# shield.net
KiCad netlist of a schematic drawn in EAGLE
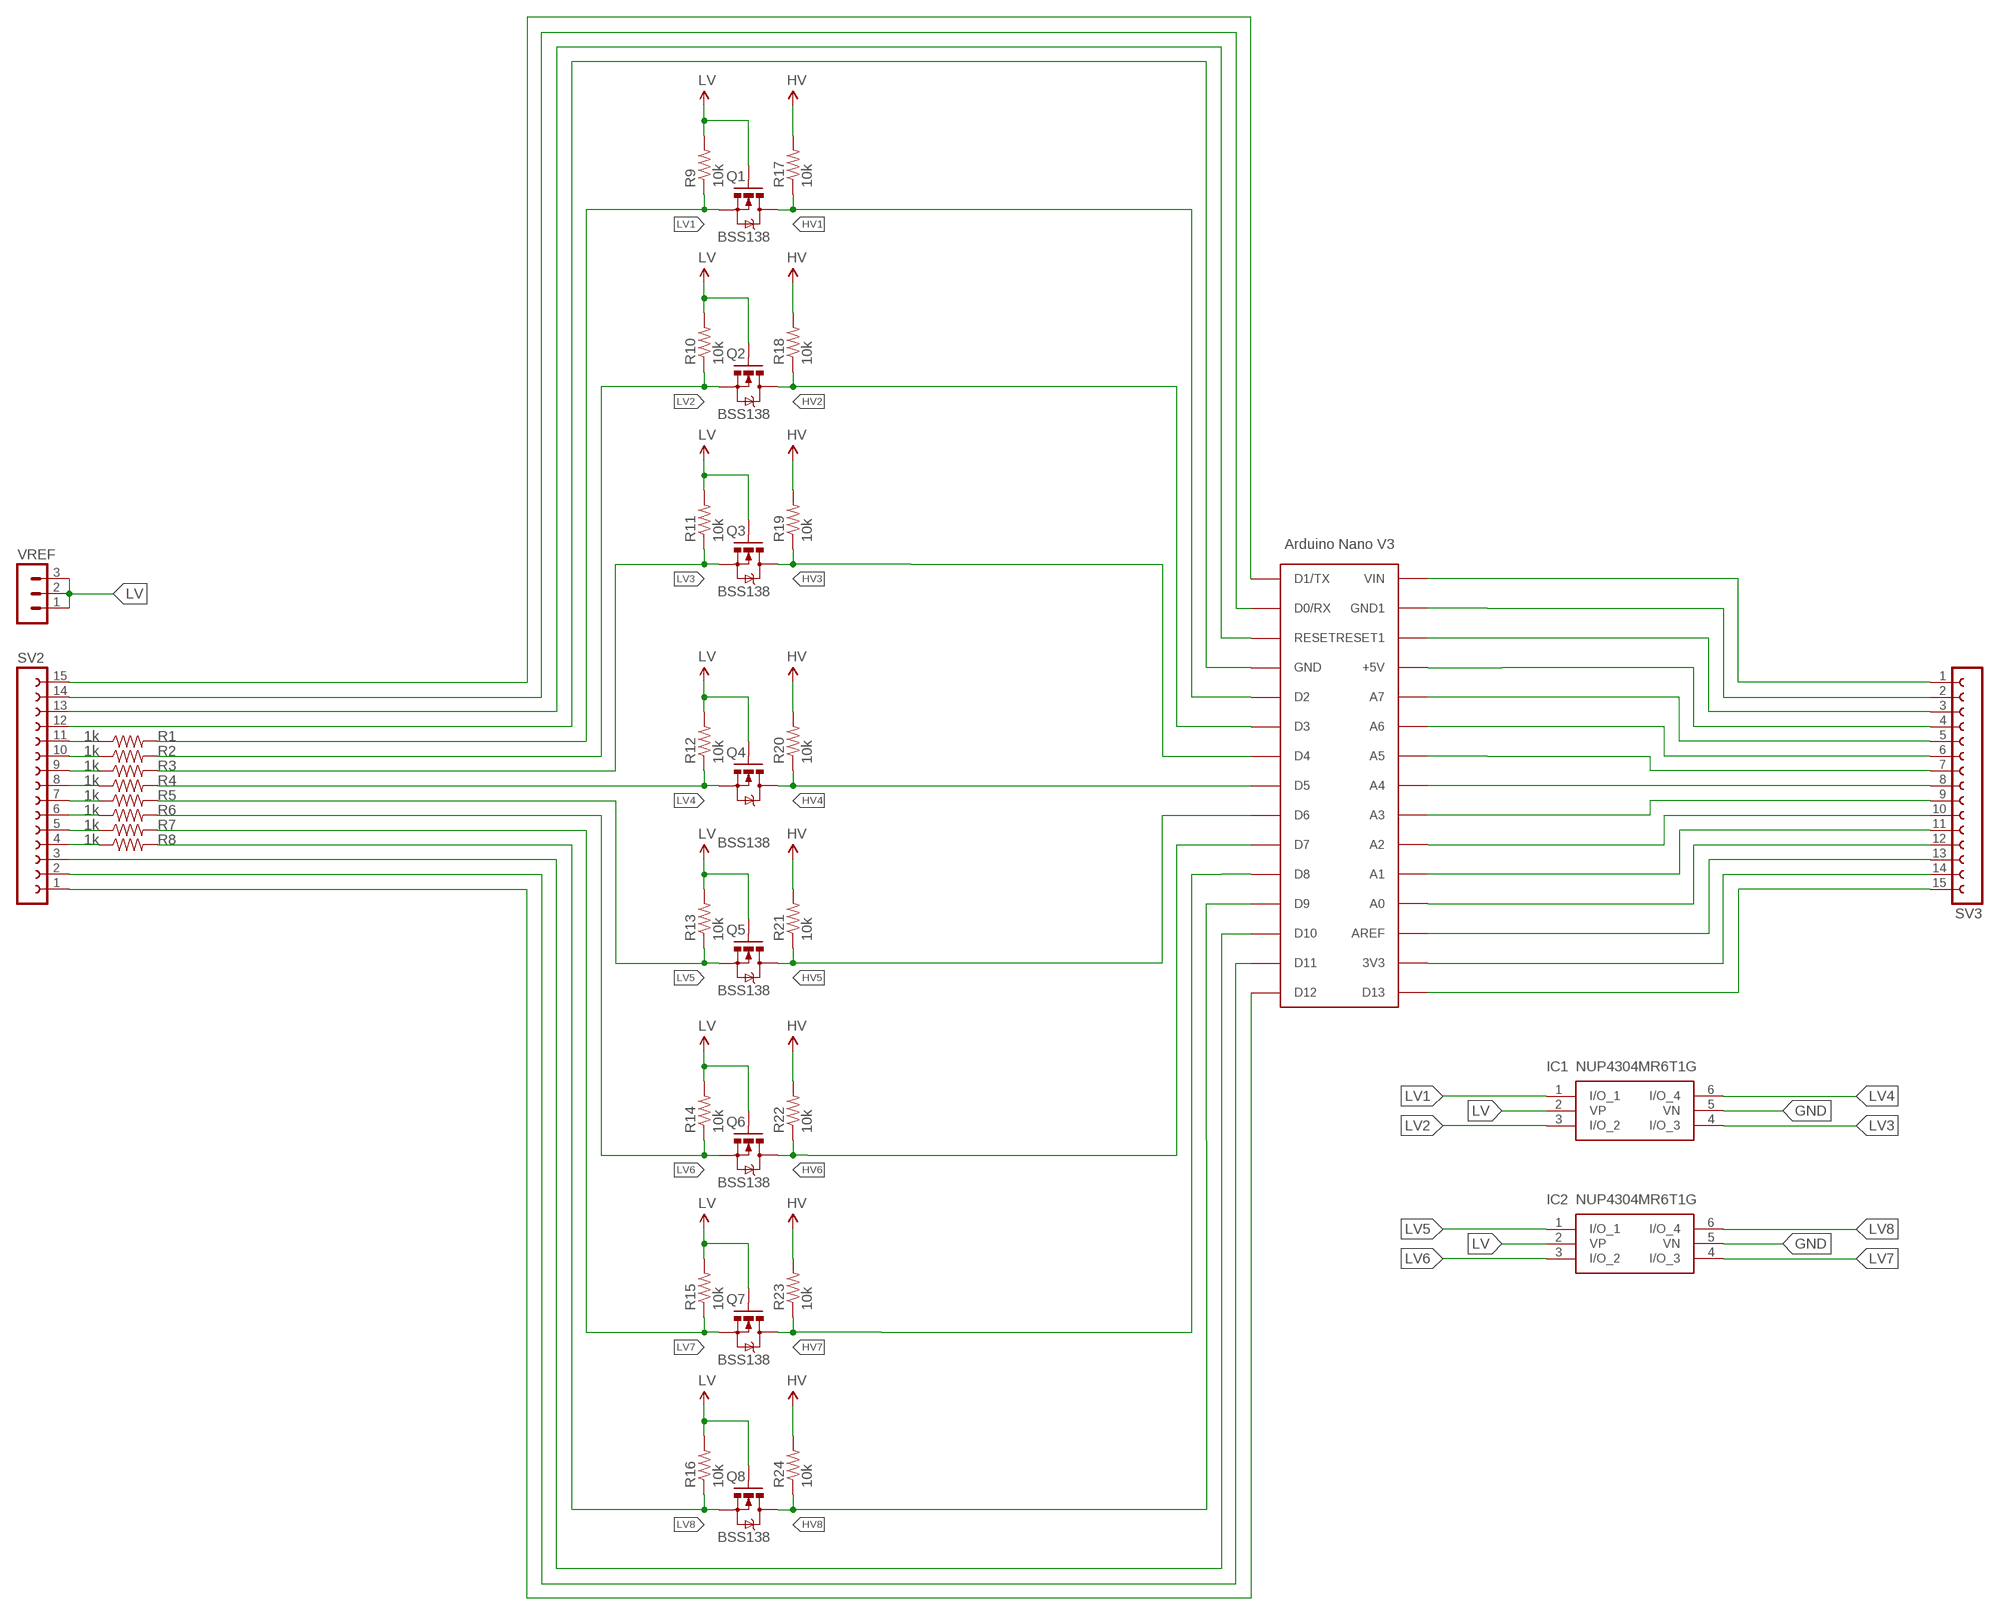
[diagram p0: schematic, sheet 1]

(export (version "E")
  (design (tool "Eeschema 10.0.6"))
  (components
    (comp (ref "IC1")
      (value "NUP4304MR6T1G")
      (footprint "eagle-import:SOT95P275X110-6N")
      (fields
        (field (name "MOUSER_PART_NUMBER") "863-NUP4304MR6T1G")
        (field (name "RS_PART_NUMBER") "8024310")
      )
      (libsource (lib "eagle-import") (part "NUP4304MR6T1G"))
    )
    (comp (ref "IC2")
      (value "NUP4304MR6T1G")
      (footprint "eagle-import:SOT95P275X110-6N")
      (fields
        (field (name "MOUSER_PART_NUMBER") "863-NUP4304MR6T1G")
        (field (name "RS_PART_NUMBER") "8024310")
      )
      (libsource (lib "eagle-import") (part "NUP4304MR6T1G"))
    )
    (comp (ref "Q1")
      (value "BSS138")
      (footprint "eagle-import:SOT23-3")
      (libsource (lib "eagle-import") (part "MOSFET-NCHANNELSMD"))
    )
    (comp (ref "Q2")
      (value "BSS138")
      (footprint "eagle-import:SOT23-3")
      (libsource (lib "eagle-import") (part "MOSFET-NCHANNELSMD"))
    )
    (comp (ref "Q3")
      (value "BSS138")
      (footprint "eagle-import:SOT23-3")
      (libsource (lib "eagle-import") (part "MOSFET-NCHANNELSMD"))
    )
    (comp (ref "Q4")
      (value "BSS138")
      (footprint "eagle-import:SOT23-3")
      (libsource (lib "eagle-import") (part "MOSFET-NCHANNELSMD"))
    )
    (comp (ref "Q5")
      (value "BSS138")
      (footprint "eagle-import:SOT23-3")
      (libsource (lib "eagle-import") (part "MOSFET-NCHANNELSMD"))
    )
    (comp (ref "Q6")
      (value "BSS138")
      (footprint "eagle-import:SOT23-3")
      (libsource (lib "eagle-import") (part "MOSFET-NCHANNELSMD"))
    )
    (comp (ref "Q7")
      (value "BSS138")
      (footprint "eagle-import:SOT23-3")
      (libsource (lib "eagle-import") (part "MOSFET-NCHANNELSMD"))
    )
    (comp (ref "Q8")
      (value "BSS138")
      (footprint "eagle-import:SOT23-3")
      (libsource (lib "eagle-import") (part "MOSFET-NCHANNELSMD"))
    )
    (comp (ref "R1")
      (value "1k")
      (footprint "eagle-import:R0402")
      (libsource (lib "eagle-import") (part "R-US_R0402"))
    )
    (comp (ref "R2")
      (value "1k")
      (footprint "eagle-import:R0402")
      (libsource (lib "eagle-import") (part "R-US_R0402"))
    )
    (comp (ref "R3")
      (value "1k")
      (footprint "eagle-import:R0402")
      (libsource (lib "eagle-import") (part "R-US_R0402"))
    )
    (comp (ref "R4")
      (value "1k")
      (footprint "eagle-import:R0402")
      (libsource (lib "eagle-import") (part "R-US_R0402"))
    )
    (comp (ref "R5")
      (value "1k")
      (footprint "eagle-import:R0402")
      (libsource (lib "eagle-import") (part "R-US_R0402"))
    )
    (comp (ref "R6")
      (value "1k")
      (footprint "eagle-import:R0402")
      (libsource (lib "eagle-import") (part "R-US_R0402"))
    )
    (comp (ref "R7")
      (value "1k")
      (footprint "eagle-import:R0402")
      (libsource (lib "eagle-import") (part "R-US_R0402"))
    )
    (comp (ref "R8")
      (value "1k")
      (footprint "eagle-import:R0402")
      (libsource (lib "eagle-import") (part "R-US_R0402"))
    )
    (comp (ref "R9")
      (value "10k")
      (footprint "eagle-import:R0402")
      (libsource (lib "eagle-import") (part "R-US_R0402"))
    )
    (comp (ref "R10")
      (value "10k")
      (footprint "eagle-import:R0402")
      (libsource (lib "eagle-import") (part "R-US_R0402"))
    )
    (comp (ref "R11")
      (value "10k")
      (footprint "eagle-import:R0402")
      (libsource (lib "eagle-import") (part "R-US_R0402"))
    )
    (comp (ref "R12")
      (value "10k")
      (footprint "eagle-import:R0402")
      (libsource (lib "eagle-import") (part "R-US_R0402"))
    )
    (comp (ref "R13")
      (value "10k")
      (footprint "eagle-import:R0402")
      (libsource (lib "eagle-import") (part "R-US_R0402"))
    )
    (comp (ref "R14")
      (value "10k")
      (footprint "eagle-import:R0402")
      (libsource (lib "eagle-import") (part "R-US_R0402"))
    )
    (comp (ref "R15")
      (value "10k")
      (footprint "eagle-import:R0402")
      (libsource (lib "eagle-import") (part "R-US_R0402"))
    )
    (comp (ref "R16")
      (value "10k")
      (footprint "eagle-import:R0402")
      (libsource (lib "eagle-import") (part "R-US_R0402"))
    )
    (comp (ref "R17")
      (value "10k")
      (footprint "eagle-import:R0402")
      (libsource (lib "eagle-import") (part "R-US_R0402"))
    )
    (comp (ref "R18")
      (value "10k")
      (footprint "eagle-import:R0402")
      (libsource (lib "eagle-import") (part "R-US_R0402"))
    )
    (comp (ref "R19")
      (value "10k")
      (footprint "eagle-import:R0402")
      (libsource (lib "eagle-import") (part "R-US_R0402"))
    )
    (comp (ref "R20")
      (value "10k")
      (footprint "eagle-import:R0402")
      (libsource (lib "eagle-import") (part "R-US_R0402"))
    )
    (comp (ref "R21")
      (value "10k")
      (footprint "eagle-import:R0402")
      (libsource (lib "eagle-import") (part "R-US_R0402"))
    )
    (comp (ref "R22")
      (value "10k")
      (footprint "eagle-import:R0402")
      (libsource (lib "eagle-import") (part "R-US_R0402"))
    )
    (comp (ref "R23")
      (value "10k")
      (footprint "eagle-import:R0402")
      (libsource (lib "eagle-import") (part "R-US_R0402"))
    )
    (comp (ref "R24")
      (value "10k")
      (footprint "eagle-import:R0402")
      (libsource (lib "eagle-import") (part "R-US_R0402"))
    )
    (comp (ref "SV2")
      (value "FE15-1")
      (footprint "eagle-import:FE15")
      (libsource (lib "eagle-import") (part "FE15-1"))
    )
    (comp (ref "SV3")
      (value "FE15-1")
      (footprint "eagle-import:FE15")
      (libsource (lib "eagle-import") (part "FE15-1"))
    )
    (comp (ref "U1")
      (value "CRE-LIB1-NL_ARDUINONANO40-MIL-HOLES")
      (footprint "eagle-import:ARDUINO-NANO-32-40MIL-HOLES")
      (libsource (lib "eagle-import") (part "CRE-LIB1-NL_ARDUINONANO40-MIL-HOLES"))
    )
    (comp (ref "VREF")
      (value "MA03-1")
      (footprint "eagle-import:MA03-1")
      (libsource (lib "eagle-import") (part "MA03-1"))
    )
  )
  (nets
    (net (code "1") (name "GND") (class "Default")
      (node (ref "IC1") (pin "5") (pinfunction "VN_5") (pintype "bidirectional"))
      (node (ref "IC2") (pin "5") (pinfunction "VN_5") (pintype "bidirectional"))
      (node (ref "SV2") (pin "12") (pinfunction "12_12") (pintype "passive"))
      (node (ref "SV3") (pin "2") (pinfunction "2_2") (pintype "passive"))
      (node (ref "U1") (pin "GND") (pinfunction "GND_GND") (pintype "bidirectional"))
      (node (ref "U1") (pin "GND1") (pinfunction "GND1_GND1") (pintype "bidirectional"))
    )
    (net (code "2") (name "HV") (class "Default")
      (node (ref "R17") (pin "2") (pinfunction "2_2") (pintype "passive"))
      (node (ref "R18") (pin "2") (pinfunction "2_2") (pintype "passive"))
      (node (ref "R19") (pin "2") (pinfunction "2_2") (pintype "passive"))
      (node (ref "R20") (pin "2") (pinfunction "2_2") (pintype "passive"))
      (node (ref "R21") (pin "2") (pinfunction "2_2") (pintype "passive"))
      (node (ref "R22") (pin "2") (pinfunction "2_2") (pintype "passive"))
      (node (ref "R23") (pin "2") (pinfunction "2_2") (pintype "passive"))
      (node (ref "R24") (pin "2") (pinfunction "2_2") (pintype "passive"))
      (node (ref "SV3") (pin "4") (pinfunction "4_4") (pintype "passive"))
      (node (ref "U1") (pin "+5V") (pinfunction "+5V_+5V") (pintype "bidirectional"))
    )
    (net (code "3") (name "HV1") (class "Default")
      (node (ref "Q1") (pin "3") (pinfunction "D_3") (pintype "passive"))
      (node (ref "R17") (pin "1") (pinfunction "1_1") (pintype "passive"))
      (node (ref "U1") (pin "D2") (pinfunction "D2_D2") (pintype "bidirectional"))
    )
    (net (code "4") (name "HV2") (class "Default")
      (node (ref "Q2") (pin "3") (pinfunction "D_3") (pintype "passive"))
      (node (ref "R18") (pin "1") (pinfunction "1_1") (pintype "passive"))
      (node (ref "U1") (pin "D3") (pinfunction "D3_D3") (pintype "bidirectional"))
    )
    (net (code "5") (name "HV3") (class "Default")
      (node (ref "Q3") (pin "3") (pinfunction "D_3") (pintype "passive"))
      (node (ref "R19") (pin "1") (pinfunction "1_1") (pintype "passive"))
      (node (ref "U1") (pin "D4") (pinfunction "D4_D4") (pintype "bidirectional"))
    )
    (net (code "6") (name "HV4") (class "Default")
      (node (ref "Q4") (pin "3") (pinfunction "D_3") (pintype "passive"))
      (node (ref "R20") (pin "1") (pinfunction "1_1") (pintype "passive"))
      (node (ref "U1") (pin "D5") (pinfunction "D5_D5") (pintype "bidirectional"))
    )
    (net (code "7") (name "HV5") (class "Default")
      (node (ref "Q5") (pin "3") (pinfunction "D_3") (pintype "passive"))
      (node (ref "R21") (pin "1") (pinfunction "1_1") (pintype "passive"))
      (node (ref "U1") (pin "D6") (pinfunction "D6_D6") (pintype "bidirectional"))
    )
    (net (code "8") (name "HV6") (class "Default")
      (node (ref "Q6") (pin "3") (pinfunction "D_3") (pintype "passive"))
      (node (ref "R22") (pin "1") (pinfunction "1_1") (pintype "passive"))
      (node (ref "U1") (pin "D7") (pinfunction "D7_D7") (pintype "bidirectional"))
    )
    (net (code "9") (name "HV7") (class "Default")
      (node (ref "Q7") (pin "3") (pinfunction "D_3") (pintype "passive"))
      (node (ref "R23") (pin "1") (pinfunction "1_1") (pintype "passive"))
      (node (ref "U1") (pin "D8") (pinfunction "D8_D8") (pintype "bidirectional"))
    )
    (net (code "10") (name "HV8") (class "Default")
      (node (ref "Q8") (pin "3") (pinfunction "D_3") (pintype "passive"))
      (node (ref "R24") (pin "1") (pinfunction "1_1") (pintype "passive"))
      (node (ref "U1") (pin "D9") (pinfunction "D9_D9") (pintype "bidirectional"))
    )
    (net (code "11") (name "LV") (class "Default")
      (node (ref "IC1") (pin "2") (pinfunction "VP_2") (pintype "bidirectional"))
      (node (ref "IC2") (pin "2") (pinfunction "VP_2") (pintype "bidirectional"))
      (node (ref "Q1") (pin "1") (pinfunction "G_1") (pintype "passive"))
      (node (ref "Q2") (pin "1") (pinfunction "G_1") (pintype "passive"))
      (node (ref "Q3") (pin "1") (pinfunction "G_1") (pintype "passive"))
      (node (ref "Q4") (pin "1") (pinfunction "G_1") (pintype "passive"))
      (node (ref "Q5") (pin "1") (pinfunction "G_1") (pintype "passive"))
      (node (ref "Q6") (pin "1") (pinfunction "G_1") (pintype "passive"))
      (node (ref "Q7") (pin "1") (pinfunction "G_1") (pintype "passive"))
      (node (ref "Q8") (pin "1") (pinfunction "G_1") (pintype "passive"))
      (node (ref "R10") (pin "2") (pinfunction "2_2") (pintype "passive"))
      (node (ref "R11") (pin "2") (pinfunction "2_2") (pintype "passive"))
      (node (ref "R12") (pin "2") (pinfunction "2_2") (pintype "passive"))
      (node (ref "R13") (pin "2") (pinfunction "2_2") (pintype "passive"))
      (node (ref "R14") (pin "2") (pinfunction "2_2") (pintype "passive"))
      (node (ref "R15") (pin "2") (pinfunction "2_2") (pintype "passive"))
      (node (ref "R16") (pin "2") (pinfunction "2_2") (pintype "passive"))
      (node (ref "R9") (pin "2") (pinfunction "2_2") (pintype "passive"))
      (node (ref "VREF") (pin "1") (pinfunction "1_1") (pintype "passive"))
      (node (ref "VREF") (pin "2") (pinfunction "2_2") (pintype "passive"))
      (node (ref "VREF") (pin "3") (pinfunction "3_3") (pintype "passive"))
    )
    (net (code "12") (name "LV1") (class "Default")
      (node (ref "IC1") (pin "1") (pinfunction "I/O_1_1") (pintype "bidirectional"))
      (node (ref "Q1") (pin "2") (pinfunction "S_2") (pintype "passive"))
      (node (ref "R1") (pin "2") (pinfunction "2_2") (pintype "passive"))
      (node (ref "R9") (pin "1") (pinfunction "1_1") (pintype "passive"))
    )
    (net (code "13") (name "LV2") (class "Default")
      (node (ref "IC1") (pin "3") (pinfunction "I/O_2_3") (pintype "bidirectional"))
      (node (ref "Q2") (pin "2") (pinfunction "S_2") (pintype "passive"))
      (node (ref "R10") (pin "1") (pinfunction "1_1") (pintype "passive"))
      (node (ref "R2") (pin "2") (pinfunction "2_2") (pintype "passive"))
    )
    (net (code "14") (name "LV3") (class "Default")
      (node (ref "IC1") (pin "4") (pinfunction "I/O_3_4") (pintype "bidirectional"))
      (node (ref "Q3") (pin "2") (pinfunction "S_2") (pintype "passive"))
      (node (ref "R11") (pin "1") (pinfunction "1_1") (pintype "passive"))
      (node (ref "R3") (pin "2") (pinfunction "2_2") (pintype "passive"))
    )
    (net (code "15") (name "LV4") (class "Default")
      (node (ref "IC1") (pin "6") (pinfunction "I/O_4_6") (pintype "bidirectional"))
      (node (ref "Q4") (pin "2") (pinfunction "S_2") (pintype "passive"))
      (node (ref "R12") (pin "1") (pinfunction "1_1") (pintype "passive"))
      (node (ref "R4") (pin "2") (pinfunction "2_2") (pintype "passive"))
    )
    (net (code "16") (name "LV5") (class "Default")
      (node (ref "IC2") (pin "1") (pinfunction "I/O_1_1") (pintype "bidirectional"))
      (node (ref "Q5") (pin "2") (pinfunction "S_2") (pintype "passive"))
      (node (ref "R13") (pin "1") (pinfunction "1_1") (pintype "passive"))
      (node (ref "R5") (pin "2") (pinfunction "2_2") (pintype "passive"))
    )
    (net (code "17") (name "LV6") (class "Default")
      (node (ref "IC2") (pin "3") (pinfunction "I/O_2_3") (pintype "bidirectional"))
      (node (ref "Q6") (pin "2") (pinfunction "S_2") (pintype "passive"))
      (node (ref "R14") (pin "1") (pinfunction "1_1") (pintype "passive"))
      (node (ref "R6") (pin "2") (pinfunction "2_2") (pintype "passive"))
    )
    (net (code "18") (name "LV7") (class "Default")
      (node (ref "IC2") (pin "4") (pinfunction "I/O_3_4") (pintype "bidirectional"))
      (node (ref "Q7") (pin "2") (pinfunction "S_2") (pintype "passive"))
      (node (ref "R15") (pin "1") (pinfunction "1_1") (pintype "passive"))
      (node (ref "R7") (pin "2") (pinfunction "2_2") (pintype "passive"))
    )
    (net (code "19") (name "LV8") (class "Default")
      (node (ref "IC2") (pin "6") (pinfunction "I/O_4_6") (pintype "bidirectional"))
      (node (ref "Q8") (pin "2") (pinfunction "S_2") (pintype "passive"))
      (node (ref "R16") (pin "1") (pinfunction "1_1") (pintype "passive"))
      (node (ref "R8") (pin "2") (pinfunction "2_2") (pintype "passive"))
    )
    (net (code "20") (name "Net-(R1-Pad1)") (class "Default")
      (node (ref "R1") (pin "1") (pinfunction "1_1") (pintype "passive"))
      (node (ref "SV2") (pin "11") (pinfunction "11_11") (pintype "passive"))
    )
    (net (code "21") (name "Net-(R2-Pad1)") (class "Default")
      (node (ref "R2") (pin "1") (pinfunction "1_1") (pintype "passive"))
      (node (ref "SV2") (pin "10") (pinfunction "10_10") (pintype "passive"))
    )
    (net (code "22") (name "Net-(R3-Pad1)") (class "Default")
      (node (ref "R3") (pin "1") (pinfunction "1_1") (pintype "passive"))
      (node (ref "SV2") (pin "9") (pinfunction "9_9") (pintype "passive"))
    )
    (net (code "23") (name "Net-(R4-Pad1)") (class "Default")
      (node (ref "R4") (pin "1") (pinfunction "1_1") (pintype "passive"))
      (node (ref "SV2") (pin "8") (pinfunction "8_8") (pintype "passive"))
    )
    (net (code "24") (name "Net-(R5-Pad1)") (class "Default")
      (node (ref "R5") (pin "1") (pinfunction "1_1") (pintype "passive"))
      (node (ref "SV2") (pin "7") (pinfunction "7_7") (pintype "passive"))
    )
    (net (code "25") (name "Net-(R6-Pad1)") (class "Default")
      (node (ref "R6") (pin "1") (pinfunction "1_1") (pintype "passive"))
      (node (ref "SV2") (pin "6") (pinfunction "6_6") (pintype "passive"))
    )
    (net (code "26") (name "Net-(R7-Pad1)") (class "Default")
      (node (ref "R7") (pin "1") (pinfunction "1_1") (pintype "passive"))
      (node (ref "SV2") (pin "5") (pinfunction "5_5") (pintype "passive"))
    )
    (net (code "27") (name "Net-(R8-Pad1)") (class "Default")
      (node (ref "R8") (pin "1") (pinfunction "1_1") (pintype "passive"))
      (node (ref "SV2") (pin "4") (pinfunction "4_4") (pintype "passive"))
    )
    (net (code "28") (name "Net-(SV2-Pad1)") (class "Default")
      (node (ref "SV2") (pin "1") (pinfunction "1_1") (pintype "passive"))
      (node (ref "U1") (pin "D12") (pinfunction "D12_D12") (pintype "bidirectional"))
    )
    (net (code "29") (name "Net-(SV2-Pad2)") (class "Default")
      (node (ref "SV2") (pin "2") (pinfunction "2_2") (pintype "passive"))
      (node (ref "U1") (pin "D11") (pinfunction "D11_D11") (pintype "bidirectional"))
    )
    (net (code "30") (name "Net-(SV2-Pad3)") (class "Default")
      (node (ref "SV2") (pin "3") (pinfunction "3_3") (pintype "passive"))
      (node (ref "U1") (pin "D10") (pinfunction "D10_D10") (pintype "bidirectional"))
    )
    (net (code "31") (name "Net-(SV2-Pad13)") (class "Default")
      (node (ref "SV2") (pin "13") (pinfunction "13_13") (pintype "passive"))
      (node (ref "U1") (pin "RESET") (pinfunction "RESET_RESET") (pintype "bidirectional"))
    )
    (net (code "32") (name "Net-(SV2-Pad14)") (class "Default")
      (node (ref "SV2") (pin "14") (pinfunction "14_14") (pintype "passive"))
      (node (ref "U1") (pin "D0/RX") (pinfunction "D0/RX_D0/RX") (pintype "bidirectional"))
    )
    (net (code "33") (name "Net-(SV2-Pad15)") (class "Default")
      (node (ref "SV2") (pin "15") (pinfunction "15_15") (pintype "passive"))
      (node (ref "U1") (pin "D1/TX") (pinfunction "D1/TX_D1/TX") (pintype "bidirectional"))
    )
    (net (code "34") (name "Net-(SV3-Pad1)") (class "Default")
      (node (ref "SV3") (pin "1") (pinfunction "1_1") (pintype "passive"))
      (node (ref "U1") (pin "VIN") (pinfunction "VIN_VIN") (pintype "bidirectional"))
    )
    (net (code "35") (name "Net-(SV3-Pad3)") (class "Default")
      (node (ref "SV3") (pin "3") (pinfunction "3_3") (pintype "passive"))
      (node (ref "U1") (pin "RESET1") (pinfunction "RESET1_RESET1") (pintype "bidirectional"))
    )
    (net (code "36") (name "Net-(SV3-Pad13)") (class "Default")
      (node (ref "SV3") (pin "13") (pinfunction "13_13") (pintype "passive"))
      (node (ref "U1") (pin "AREF") (pinfunction "AREF_AREF") (pintype "bidirectional"))
    )
    (net (code "37") (name "Net-(SV3-Pad14)") (class "Default")
      (node (ref "SV3") (pin "14") (pinfunction "14_14") (pintype "passive"))
      (node (ref "U1") (pin "3V3") (pinfunction "3V3_3V3") (pintype "bidirectional"))
    )
    (net (code "38") (name "Net-(SV3-Pad15)") (class "Default")
      (node (ref "SV3") (pin "15") (pinfunction "15_15") (pintype "passive"))
      (node (ref "U1") (pin "D13") (pinfunction "D13_D13") (pintype "bidirectional"))
    )
    (net (code "39") (name "Net-(U1-A0)") (class "Default")
      (node (ref "SV3") (pin "12") (pinfunction "12_12") (pintype "passive"))
      (node (ref "U1") (pin "A7") (pinfunction "A0_A7") (pintype "bidirectional"))
    )
    (net (code "40") (name "Net-(U1-A1)") (class "Default")
      (node (ref "SV3") (pin "11") (pinfunction "11_11") (pintype "passive"))
      (node (ref "U1") (pin "A6") (pinfunction "A1_A6") (pintype "bidirectional"))
    )
    (net (code "41") (name "Net-(U1-A2)") (class "Default")
      (node (ref "SV3") (pin "10") (pinfunction "10_10") (pintype "passive"))
      (node (ref "U1") (pin "A5") (pinfunction "A2_A5") (pintype "bidirectional"))
    )
    (net (code "42") (name "Net-(U1-A3)") (class "Default")
      (node (ref "SV3") (pin "9") (pinfunction "9_9") (pintype "passive"))
      (node (ref "U1") (pin "A4") (pinfunction "A3_A4") (pintype "bidirectional"))
    )
    (net (code "43") (name "Net-(U1-A4)") (class "Default")
      (node (ref "SV3") (pin "8") (pinfunction "8_8") (pintype "passive"))
      (node (ref "U1") (pin "A3") (pinfunction "A4_A3") (pintype "bidirectional"))
    )
    (net (code "44") (name "Net-(U1-A5)") (class "Default")
      (node (ref "SV3") (pin "7") (pinfunction "7_7") (pintype "passive"))
      (node (ref "U1") (pin "A2") (pinfunction "A5_A2") (pintype "bidirectional"))
    )
    (net (code "45") (name "Net-(U1-A6)") (class "Default")
      (node (ref "SV3") (pin "6") (pinfunction "6_6") (pintype "passive"))
      (node (ref "U1") (pin "A1") (pinfunction "A6_A1") (pintype "bidirectional"))
    )
    (net (code "46") (name "Net-(U1-A7)") (class "Default")
      (node (ref "SV3") (pin "5") (pinfunction "5_5") (pintype "passive"))
      (node (ref "U1") (pin "A0") (pinfunction "A7_A0") (pintype "bidirectional"))
    )
  )
)
